# me433_2017.net
KiCad netlist of a schematic drawn in EAGLE
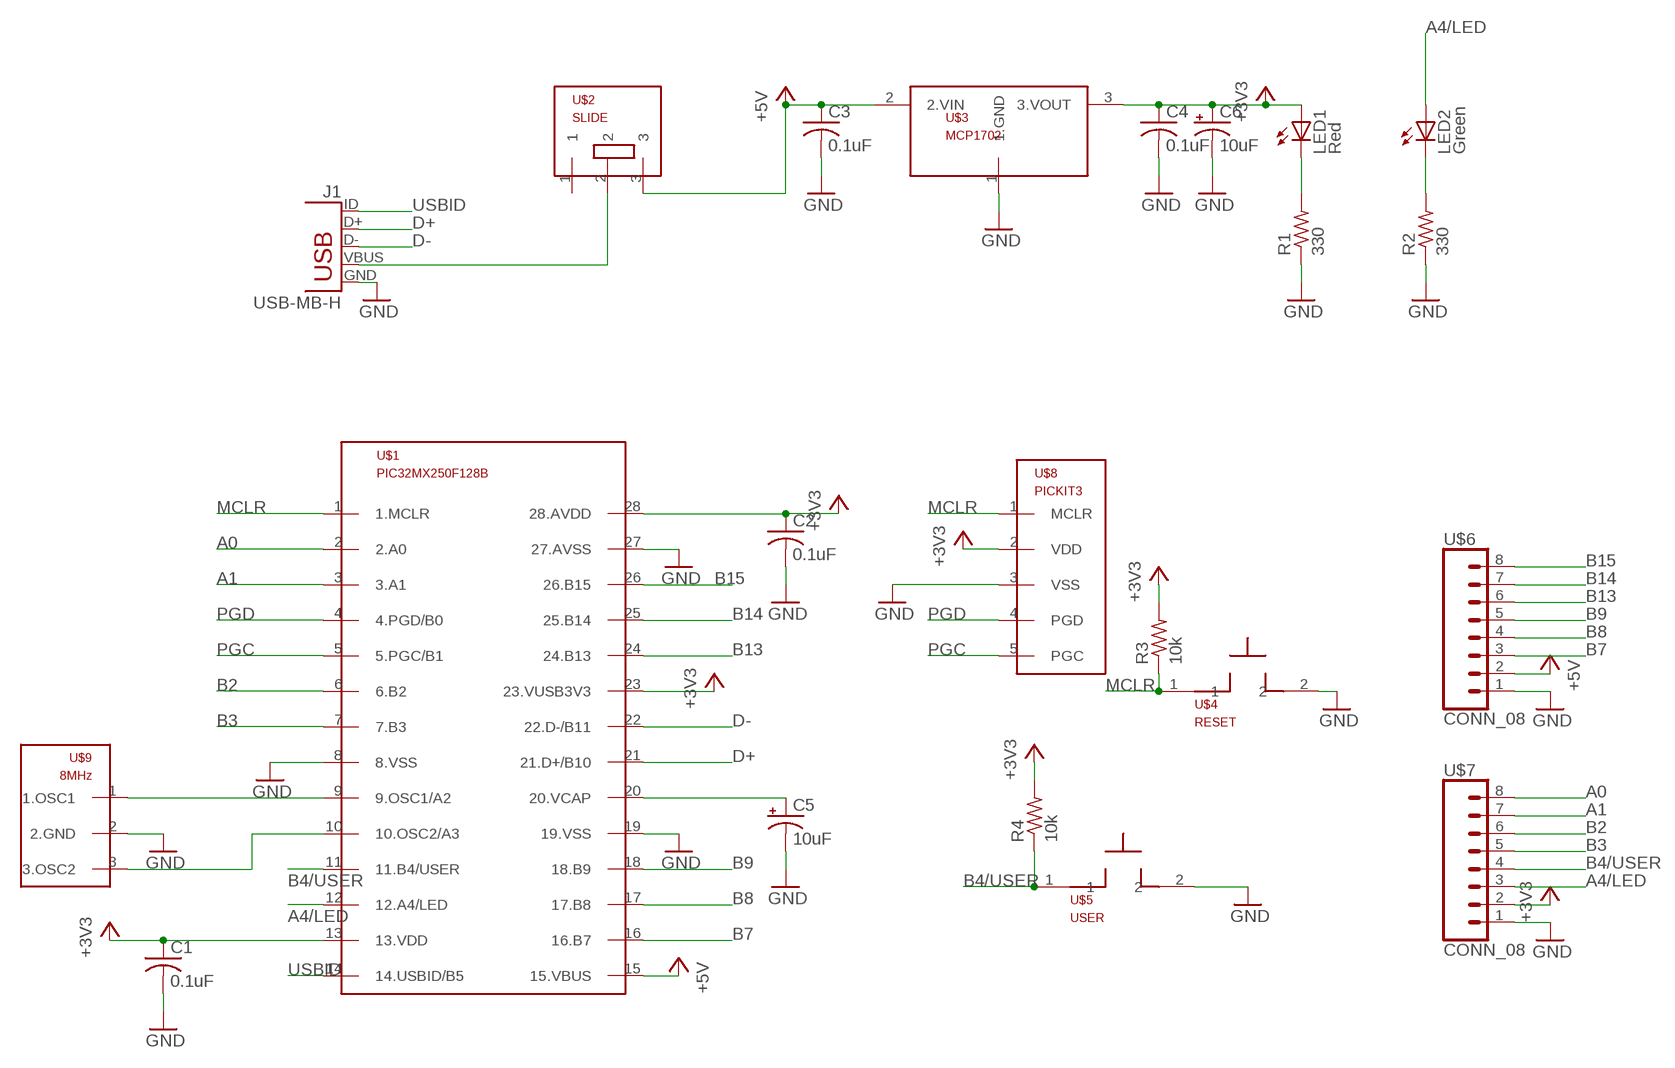
[diagram p0: schematic, sheet 1]

(export (version "E")
  (design (tool "Eeschema 10.0.6"))
  (components
    (comp (ref "C1")
      (value "0.1uF")
      (footprint "eagle-import:C025-025X050")
      (libsource (lib "eagle-import") (part "C-US025-025X050"))
    )
    (comp (ref "C2")
      (value "0.1uF")
      (footprint "eagle-import:C025-025X050")
      (libsource (lib "eagle-import") (part "C-US025-025X050"))
    )
    (comp (ref "C3")
      (value "0.1uF")
      (footprint "eagle-import:C025-025X050")
      (libsource (lib "eagle-import") (part "C-US025-025X050"))
    )
    (comp (ref "C4")
      (value "0.1uF")
      (footprint "eagle-import:C025-025X050")
      (libsource (lib "eagle-import") (part "C-US025-025X050"))
    )
    (comp (ref "C5")
      (value "10uF")
      (footprint "eagle-import:B45181B")
      (libsource (lib "eagle-import") (part "CPOL-USB45181B"))
    )
    (comp (ref "C6")
      (value "10uF")
      (footprint "eagle-import:B45181B")
      (libsource (lib "eagle-import") (part "CPOL-USB45181B"))
    )
    (comp (ref "J1")
      (value "USB-MB-H")
      (footprint "eagle-import:USB-MB-H")
      (libsource (lib "eagle-import") (part "USB-MB-H"))
    )
    (comp (ref "LED1")
      (value "Red")
      (footprint "eagle-import:LED3MM")
      (libsource (lib "eagle-import") (part "LED3MM"))
    )
    (comp (ref "LED2")
      (value "Green")
      (footprint "eagle-import:LED3MM")
      (libsource (lib "eagle-import") (part "LED3MM"))
    )
    (comp (ref "R1")
      (value "330")
      (footprint "eagle-import:0207_10")
      (libsource (lib "eagle-import") (part "R-US_0207/10"))
    )
    (comp (ref "R2")
      (value "330")
      (footprint "eagle-import:0207_10")
      (libsource (lib "eagle-import") (part "R-US_0207/10"))
    )
    (comp (ref "R3")
      (value "10k")
      (footprint "eagle-import:0207_10")
      (libsource (lib "eagle-import") (part "R-US_0207/10"))
    )
    (comp (ref "R4")
      (value "10k")
      (footprint "eagle-import:0207_10")
      (libsource (lib "eagle-import") (part "R-US_0207/10"))
    )
    (comp (ref "U$1")
      (value "PIC32MX250F128B")
      (footprint "eagle-import:DIL28-3")
      (libsource (lib "eagle-import") (part "PIC32MX250F128B"))
    )
    (comp (ref "U$2")
      (value "SLIDE")
      (footprint "eagle-import:SLIDE")
      (libsource (lib "eagle-import") (part "SLIDE"))
    )
    (comp (ref "U$3")
      (value "MCP1702")
      (footprint "eagle-import:TO92")
      (libsource (lib "eagle-import") (part "MCP1702"))
    )
    (comp (ref "U$4")
      (value "RESET")
      (footprint "eagle-import:PB")
      (libsource (lib "eagle-import") (part "PB"))
    )
    (comp (ref "U$5")
      (value "USER")
      (footprint "eagle-import:PB")
      (libsource (lib "eagle-import") (part "PB"))
    )
    (comp (ref "U$6")
      (value "CONN_08")
      (footprint "eagle-import:1X08")
      (libsource (lib "eagle-import") (part "CONN_08"))
    )
    (comp (ref "U$7")
      (value "CONN_08")
      (footprint "eagle-import:1X08")
      (libsource (lib "eagle-import") (part "CONN_08"))
    )
    (comp (ref "U$8")
      (value "PICKIT3")
      (footprint "eagle-import:1X05")
      (libsource (lib "eagle-import") (part "PICKIT3"))
    )
    (comp (ref "U$9")
      (value "8MHz")
      (footprint "eagle-import:OSC")
      (libsource (lib "eagle-import") (part "OSC"))
    )
  )
  (nets
    (net (code "1") (name "+3V3") (class "Default")
      (node (ref "C1") (pin "1") (pinfunction "1_1") (pintype "passive"))
      (node (ref "C2") (pin "1") (pinfunction "1_1") (pintype "passive"))
      (node (ref "C4") (pin "1") (pinfunction "1_1") (pintype "passive"))
      (node (ref "C6") (pin "+") (pinfunction "+_+") (pintype "passive"))
      (node (ref "LED1") (pin "A") (pinfunction "A_A") (pintype "passive"))
      (node (ref "R3") (pin "2") (pinfunction "2_2") (pintype "passive"))
      (node (ref "R4") (pin "2") (pinfunction "2_2") (pintype "passive"))
      (node (ref "U$1") (pin "13") (pinfunction "13.VDD_13") (pintype "bidirectional"))
      (node (ref "U$1") (pin "23") (pinfunction "23.VUSB3V3_23") (pintype "bidirectional"))
      (node (ref "U$1") (pin "28") (pinfunction "28.AVDD_28") (pintype "bidirectional"))
      (node (ref "U$3") (pin "3") (pinfunction "3.VOUT_3") (pintype "bidirectional"))
      (node (ref "U$7") (pin "2") (pinfunction "2_2") (pintype "passive"))
      (node (ref "U$8") (pin "2") (pinfunction "VDD_2") (pintype "bidirectional"))
    )
    (net (code "2") (name "+5V") (class "Default")
      (node (ref "C3") (pin "1") (pinfunction "1_1") (pintype "passive"))
      (node (ref "U$1") (pin "15") (pinfunction "15.VBUS_15") (pintype "bidirectional"))
      (node (ref "U$2") (pin "3") (pinfunction "3_3") (pintype "bidirectional"))
      (node (ref "U$3") (pin "2") (pinfunction "2.VIN_2") (pintype "bidirectional"))
      (node (ref "U$6") (pin "2") (pinfunction "2_2") (pintype "passive"))
    )
    (net (code "3") (name "/A0") (class "Default")
      (node (ref "U$1") (pin "2") (pinfunction "2.A0_2") (pintype "bidirectional"))
      (node (ref "U$7") (pin "8") (pinfunction "8_8") (pintype "passive"))
    )
    (net (code "4") (name "/A1") (class "Default")
      (node (ref "U$1") (pin "3") (pinfunction "3.A1_3") (pintype "bidirectional"))
      (node (ref "U$7") (pin "7") (pinfunction "7_7") (pintype "passive"))
    )
    (net (code "5") (name "/A4{slash}LED") (class "Default")
      (node (ref "LED2") (pin "A") (pinfunction "A_A") (pintype "passive"))
      (node (ref "U$1") (pin "12") (pinfunction "12.A4/LED_12") (pintype "bidirectional"))
      (node (ref "U$7") (pin "3") (pinfunction "3_3") (pintype "passive"))
    )
    (net (code "6") (name "/B2") (class "Default")
      (node (ref "U$1") (pin "6") (pinfunction "6.B2_6") (pintype "bidirectional"))
      (node (ref "U$7") (pin "6") (pinfunction "6_6") (pintype "passive"))
    )
    (net (code "7") (name "/B3") (class "Default")
      (node (ref "U$1") (pin "7") (pinfunction "7.B3_7") (pintype "bidirectional"))
      (node (ref "U$7") (pin "5") (pinfunction "5_5") (pintype "passive"))
    )
    (net (code "8") (name "/B4{slash}USER") (class "Default")
      (node (ref "R4") (pin "1") (pinfunction "1_1") (pintype "passive"))
      (node (ref "U$1") (pin "11") (pinfunction "11.B4/USER_11") (pintype "bidirectional"))
      (node (ref "U$5") (pin "1") (pinfunction "1_1") (pintype "bidirectional"))
      (node (ref "U$7") (pin "4") (pinfunction "4_4") (pintype "passive"))
    )
    (net (code "9") (name "/B7") (class "Default")
      (node (ref "U$1") (pin "16") (pinfunction "16.B7_16") (pintype "bidirectional"))
      (node (ref "U$6") (pin "3") (pinfunction "3_3") (pintype "passive"))
    )
    (net (code "10") (name "/B8") (class "Default")
      (node (ref "U$1") (pin "17") (pinfunction "17.B8_17") (pintype "bidirectional"))
      (node (ref "U$6") (pin "4") (pinfunction "4_4") (pintype "passive"))
    )
    (net (code "11") (name "/B9") (class "Default")
      (node (ref "U$1") (pin "18") (pinfunction "18.B9_18") (pintype "bidirectional"))
      (node (ref "U$6") (pin "5") (pinfunction "5_5") (pintype "passive"))
    )
    (net (code "12") (name "/B13") (class "Default")
      (node (ref "U$1") (pin "24") (pinfunction "24.B13_24") (pintype "bidirectional"))
      (node (ref "U$6") (pin "6") (pinfunction "6_6") (pintype "passive"))
    )
    (net (code "13") (name "/B14") (class "Default")
      (node (ref "U$1") (pin "25") (pinfunction "25.B14_25") (pintype "bidirectional"))
      (node (ref "U$6") (pin "7") (pinfunction "7_7") (pintype "passive"))
    )
    (net (code "14") (name "/B15") (class "Default")
      (node (ref "U$1") (pin "26") (pinfunction "26.B15_26") (pintype "bidirectional"))
      (node (ref "U$6") (pin "8") (pinfunction "8_8") (pintype "passive"))
    )
    (net (code "15") (name "/D+") (class "Default")
      (node (ref "J1") (pin "D+") (pinfunction "D+_D+") (pintype "bidirectional"))
      (node (ref "U$1") (pin "21") (pinfunction "21.D+/B10_21") (pintype "bidirectional"))
    )
    (net (code "16") (name "/D-") (class "Default")
      (node (ref "J1") (pin "D-") (pinfunction "D-_D-") (pintype "bidirectional"))
      (node (ref "U$1") (pin "22") (pinfunction "22.D-/B11_22") (pintype "bidirectional"))
    )
    (net (code "17") (name "/MCLR") (class "Default")
      (node (ref "R3") (pin "1") (pinfunction "1_1") (pintype "passive"))
      (node (ref "U$1") (pin "1") (pinfunction "1.MCLR_1") (pintype "bidirectional"))
      (node (ref "U$4") (pin "1") (pinfunction "1_1") (pintype "bidirectional"))
      (node (ref "U$8") (pin "1") (pinfunction "MCLR_1") (pintype "bidirectional"))
    )
    (net (code "18") (name "/PGC") (class "Default")
      (node (ref "U$1") (pin "5") (pinfunction "5.PGC/B1_5") (pintype "bidirectional"))
      (node (ref "U$8") (pin "5") (pinfunction "PGC_5") (pintype "bidirectional"))
    )
    (net (code "19") (name "/PGD") (class "Default")
      (node (ref "U$1") (pin "4") (pinfunction "4.PGD/B0_4") (pintype "bidirectional"))
      (node (ref "U$8") (pin "4") (pinfunction "PGD_4") (pintype "bidirectional"))
    )
    (net (code "20") (name "/USBID") (class "Default")
      (node (ref "J1") (pin "ID") (pinfunction "ID_ID") (pintype "bidirectional"))
      (node (ref "U$1") (pin "14") (pinfunction "14.USBID/B5_14") (pintype "bidirectional"))
    )
    (net (code "21") (name "GND") (class "Default")
      (node (ref "C1") (pin "2") (pinfunction "2_2") (pintype "passive"))
      (node (ref "C2") (pin "2") (pinfunction "2_2") (pintype "passive"))
      (node (ref "C3") (pin "2") (pinfunction "2_2") (pintype "passive"))
      (node (ref "C4") (pin "2") (pinfunction "2_2") (pintype "passive"))
      (node (ref "C5") (pin "-") (pinfunction "-_-") (pintype "passive"))
      (node (ref "C6") (pin "-") (pinfunction "-_-") (pintype "passive"))
      (node (ref "J1") (pin "GND") (pinfunction "GND_GND") (pintype "bidirectional"))
      (node (ref "R1") (pin "1") (pinfunction "1_1") (pintype "passive"))
      (node (ref "R2") (pin "1") (pinfunction "1_1") (pintype "passive"))
      (node (ref "U$1") (pin "19") (pinfunction "19.VSS_19") (pintype "bidirectional"))
      (node (ref "U$1") (pin "27") (pinfunction "27.AVSS_27") (pintype "bidirectional"))
      (node (ref "U$1") (pin "8") (pinfunction "8.VSS_8") (pintype "bidirectional"))
      (node (ref "U$3") (pin "1") (pinfunction "1.GND_1") (pintype "bidirectional"))
      (node (ref "U$4") (pin "2") (pinfunction "2_2") (pintype "bidirectional"))
      (node (ref "U$5") (pin "2") (pinfunction "2_2") (pintype "bidirectional"))
      (node (ref "U$6") (pin "1") (pinfunction "1_1") (pintype "passive"))
      (node (ref "U$7") (pin "1") (pinfunction "1_1") (pintype "passive"))
      (node (ref "U$8") (pin "3") (pinfunction "VSS_3") (pintype "bidirectional"))
      (node (ref "U$9") (pin "2") (pinfunction "2.GND_2") (pintype "bidirectional"))
    )
    (net (code "22") (name "Net-(J1-PadVBUS)") (class "Default")
      (node (ref "J1") (pin "VBUS") (pinfunction "VBUS_VBUS") (pintype "bidirectional"))
      (node (ref "U$2") (pin "2") (pinfunction "2_2") (pintype "bidirectional"))
    )
    (net (code "23") (name "Net-(LED1-C)") (class "Default")
      (node (ref "LED1") (pin "K") (pinfunction "C_K") (pintype "passive"))
      (node (ref "R1") (pin "2") (pinfunction "2_2") (pintype "passive"))
    )
    (net (code "24") (name "Net-(LED2-C)") (class "Default")
      (node (ref "LED2") (pin "K") (pinfunction "C_K") (pintype "passive"))
      (node (ref "R2") (pin "2") (pinfunction "2_2") (pintype "passive"))
    )
    (net (code "25") (name "Net-(U$1-9.OSC1{slash}A2)") (class "Default")
      (node (ref "U$1") (pin "9") (pinfunction "9.OSC1/A2_9") (pintype "bidirectional"))
      (node (ref "U$9") (pin "1") (pinfunction "1.OSC1_1") (pintype "bidirectional"))
    )
    (net (code "26") (name "Net-(U$1-10.OSC2{slash}A3)") (class "Default")
      (node (ref "U$1") (pin "10") (pinfunction "10.OSC2/A3_10") (pintype "bidirectional"))
      (node (ref "U$9") (pin "3") (pinfunction "3.OSC2_3") (pintype "bidirectional"))
    )
    (net (code "27") (name "Net-(U$1-20.VCAP)") (class "Default")
      (node (ref "C5") (pin "+") (pinfunction "+_+") (pintype "passive"))
      (node (ref "U$1") (pin "20") (pinfunction "20.VCAP_20") (pintype "bidirectional"))
    )
    (net (code "28") (name "unconnected-(U$2-Pad1)") (class "Default")
      (node (ref "U$2") (pin "1") (pinfunction "1_1") (pintype "bidirectional"))
    )
  )
)
